# Header.net
KiCad netlist of a schematic drawn in Altium Designer
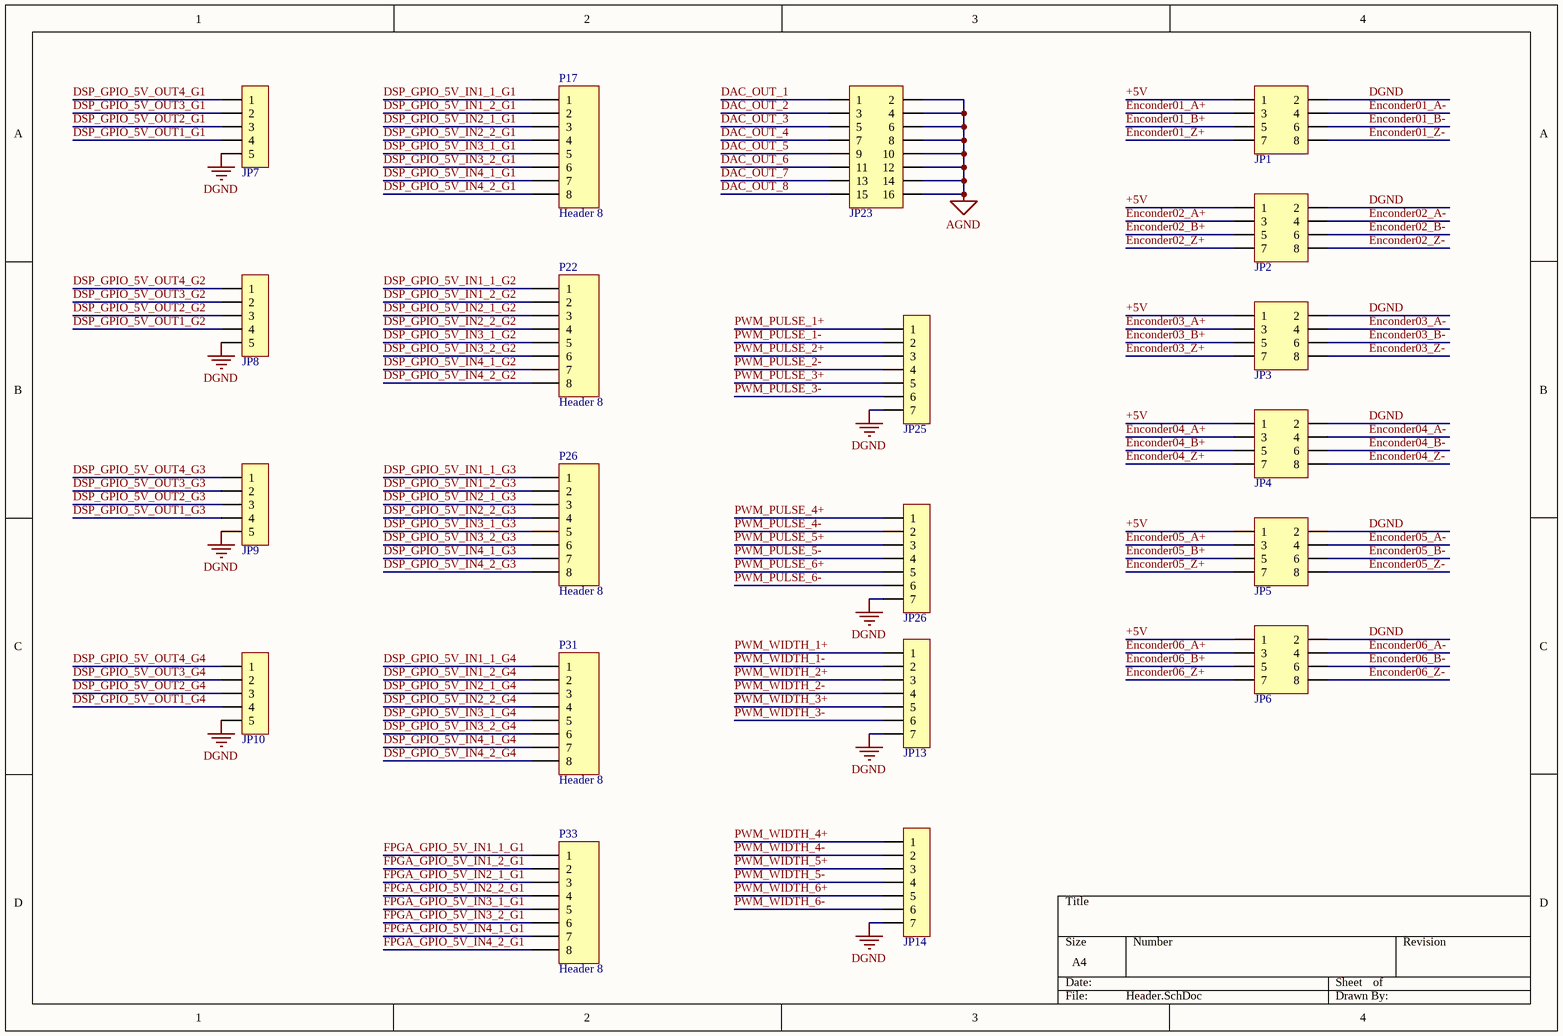
[diagram p0: Header.SchDoc]

(export (version "E")
  (design (tool "Eeschema 10.0.6"))
  (components
    (comp (ref "JP1")
      (value "Header 4X2")
      (footprint "connector5569R")
      (description "4*2P接插件")
      (fields (field (name "版权归属") "源创客"))
      (libsource (lib "4.4   - 接插件-脚距2.0") (part "Header 4X2"))
    )
    (comp (ref "JP2")
      (value "Header 4X2")
      (footprint "connector5569R")
      (description "4*2P接插件")
      (fields (field (name "版权归属") "源创客"))
      (libsource (lib "4.4   - 接插件-脚距2.0") (part "Header 4X2"))
    )
    (comp (ref "JP3")
      (value "Header 4X2")
      (footprint "connector5569R")
      (description "4*2P接插件")
      (fields (field (name "版权归属") "源创客"))
      (libsource (lib "4.4   - 接插件-脚距2.0") (part "Header 4X2"))
    )
    (comp (ref "JP4")
      (value "Header 4X2")
      (footprint "connector5569R")
      (description "4*2P接插件")
      (fields (field (name "版权归属") "源创客"))
      (libsource (lib "4.4   - 接插件-脚距2.0") (part "Header 4X2"))
    )
    (comp (ref "JP5")
      (value "Header 4X2")
      (footprint "connector5569R")
      (description "4*2P接插件")
      (fields (field (name "版权归属") "源创客"))
      (libsource (lib "4.4   - 接插件-脚距2.0") (part "Header 4X2"))
    )
    (comp (ref "JP6")
      (value "Header 4X2")
      (footprint "connector5569R")
      (description "4*2P接插件")
      (fields (field (name "版权归属") "源创客"))
      (libsource (lib "4.4   - 接插件-脚距2.0") (part "Header 4X2"))
    )
    (comp (ref "JP7")
      (value "HDR-1X5")
      (footprint "ZH1.5-WI-5P")
      (description "5P接插件")
      (fields (field (name "版权归属") "源创客"))
      (libsource (lib "4.3   - 接插件-脚距1.5") (part "Header 5"))
    )
    (comp (ref "JP8")
      (value "HDR-1X5")
      (footprint "ZH1.5-WI-5P")
      (description "5P接插件")
      (fields (field (name "版权归属") "源创客"))
      (libsource (lib "4.3   - 接插件-脚距1.5") (part "Header 5"))
    )
    (comp (ref "JP9")
      (value "HDR-1X5")
      (footprint "ZH1.5-WI-5P")
      (description "5P接插件")
      (fields (field (name "版权归属") "源创客"))
      (libsource (lib "4.3   - 接插件-脚距1.5") (part "Header 5"))
    )
    (comp (ref "JP10")
      (value "HDR-1X5")
      (footprint "ZH1.5-WI-5P")
      (description "5P接插件")
      (fields (field (name "版权归属") "源创客"))
      (libsource (lib "4.3   - 接插件-脚距1.5") (part "Header 5"))
    )
    (comp (ref "JP13")
      (value "HDR-1X7")
      (footprint "XH2.54-WI-7P")
      (description "7P接插件")
      (fields (field (name "版权归属") "源创客"))
      (libsource (lib "4.5   - 接插件-脚距2.54") (part "Header 7"))
    )
    (comp (ref "JP14")
      (value "HDR-1X7")
      (footprint "XH2.54-WI-7P")
      (description "7P接插件")
      (fields (field (name "版权归属") "源创客"))
      (libsource (lib "4.5   - 接插件-脚距2.54") (part "Header 7"))
    )
    (comp (ref "JP23")
      (value "Header 8X2")
      (footprint "connector558916pin")
      (description "8*2P接插件")
      (fields (field (name "版权归属") "源创客"))
      (libsource (lib "4.4   - 接插件-脚距2.0") (part "Header 8X2"))
    )
    (comp (ref "JP25")
      (value "HDR-1X7")
      (footprint "XH2.54-WI-7P")
      (description "7P接插件")
      (fields (field (name "版权归属") "源创客"))
      (libsource (lib "4.5   - 接插件-脚距2.54") (part "Header 7"))
    )
    (comp (ref "JP26")
      (value "HDR-1X7")
      (footprint "XH2.54-WI-7P")
      (description "7P接插件")
      (fields (field (name "版权归属") "源创客"))
      (libsource (lib "4.5   - 接插件-脚距2.54") (part "Header 7"))
    )
    (comp (ref "P17")
      (value "Header 8")
      (footprint "connector5569R")
      (description "Header, 8-Pin")
      (fields (field (name "PUBLISHER") "Altium Limited"))
      (libsource (lib "Miscellaneous Connectors") (part "Header 8"))
    )
    (comp (ref "P22")
      (value "Header 8")
      (footprint "connector5569R")
      (description "Header, 8-Pin")
      (fields (field (name "PUBLISHER") "Altium Limited"))
      (libsource (lib "Miscellaneous Connectors") (part "Header 8"))
    )
    (comp (ref "P26")
      (value "Header 8")
      (footprint "connector5569R")
      (description "Header, 8-Pin")
      (fields (field (name "PUBLISHER") "Altium Limited"))
      (libsource (lib "Miscellaneous Connectors") (part "Header 8"))
    )
    (comp (ref "P31")
      (value "Header 8")
      (footprint "connector5569R")
      (description "Header, 8-Pin")
      (fields (field (name "PUBLISHER") "Altium Limited"))
      (libsource (lib "Miscellaneous Connectors") (part "Header 8"))
    )
    (comp (ref "P33")
      (value "Header 8")
      (footprint "connector5569R")
      (description "Header, 8-Pin")
      (fields (field (name "PUBLISHER") "Altium Limited"))
      (libsource (lib "Miscellaneous Connectors") (part "Header 8"))
    )
  )
  (nets
    (net (code "1") (name "/+5V") (class "Default")
      (node (ref "JP1") (pin "1") (pinfunction "1_1") (pintype "passive"))
      (node (ref "JP2") (pin "1") (pinfunction "1_1") (pintype "passive"))
      (node (ref "JP3") (pin "1") (pinfunction "1_1") (pintype "passive"))
      (node (ref "JP4") (pin "1") (pinfunction "1_1") (pintype "passive"))
      (node (ref "JP5") (pin "1") (pinfunction "1_1") (pintype "passive"))
      (node (ref "JP6") (pin "1") (pinfunction "1_1") (pintype "passive"))
    )
    (net (code "2") (name "/DAC_OUT_1") (class "Default")
      (node (ref "JP23") (pin "1") (pinfunction "1_1") (pintype "passive"))
    )
    (net (code "3") (name "/DAC_OUT_2") (class "Default")
      (node (ref "JP23") (pin "3") (pinfunction "3_3") (pintype "passive"))
    )
    (net (code "4") (name "/DAC_OUT_3") (class "Default")
      (node (ref "JP23") (pin "5") (pinfunction "5_5") (pintype "passive"))
    )
    (net (code "5") (name "/DAC_OUT_4") (class "Default")
      (node (ref "JP23") (pin "7") (pinfunction "7_7") (pintype "passive"))
    )
    (net (code "6") (name "/DAC_OUT_5") (class "Default")
      (node (ref "JP23") (pin "9") (pinfunction "9_9") (pintype "passive"))
    )
    (net (code "7") (name "/DAC_OUT_6") (class "Default")
      (node (ref "JP23") (pin "11") (pinfunction "11_11") (pintype "passive"))
    )
    (net (code "8") (name "/DAC_OUT_7") (class "Default")
      (node (ref "JP23") (pin "13") (pinfunction "13_13") (pintype "passive"))
    )
    (net (code "9") (name "/DAC_OUT_8") (class "Default")
      (node (ref "JP23") (pin "15") (pinfunction "15_15") (pintype "passive"))
    )
    (net (code "10") (name "/DSP_GPIO_5V_IN1_1_G1") (class "Default")
      (node (ref "P17") (pin "1") (pinfunction "1_1") (pintype "passive"))
    )
    (net (code "11") (name "/DSP_GPIO_5V_IN1_1_G2") (class "Default")
      (node (ref "P22") (pin "1") (pinfunction "1_1") (pintype "passive"))
    )
    (net (code "12") (name "/DSP_GPIO_5V_IN1_1_G3") (class "Default")
      (node (ref "P26") (pin "1") (pinfunction "1_1") (pintype "passive"))
    )
    (net (code "13") (name "/DSP_GPIO_5V_IN1_1_G4") (class "Default")
      (node (ref "P31") (pin "1") (pinfunction "1_1") (pintype "passive"))
    )
    (net (code "14") (name "/DSP_GPIO_5V_IN1_2_G1") (class "Default")
      (node (ref "P17") (pin "2") (pinfunction "2_2") (pintype "passive"))
    )
    (net (code "15") (name "/DSP_GPIO_5V_IN1_2_G2") (class "Default")
      (node (ref "P22") (pin "2") (pinfunction "2_2") (pintype "passive"))
    )
    (net (code "16") (name "/DSP_GPIO_5V_IN1_2_G3") (class "Default")
      (node (ref "P26") (pin "2") (pinfunction "2_2") (pintype "passive"))
    )
    (net (code "17") (name "/DSP_GPIO_5V_IN1_2_G4") (class "Default")
      (node (ref "P31") (pin "2") (pinfunction "2_2") (pintype "passive"))
    )
    (net (code "18") (name "/DSP_GPIO_5V_IN2_1_G1") (class "Default")
      (node (ref "P17") (pin "3") (pinfunction "3_3") (pintype "passive"))
    )
    (net (code "19") (name "/DSP_GPIO_5V_IN2_1_G2") (class "Default")
      (node (ref "P22") (pin "3") (pinfunction "3_3") (pintype "passive"))
    )
    (net (code "20") (name "/DSP_GPIO_5V_IN2_1_G3") (class "Default")
      (node (ref "P26") (pin "3") (pinfunction "3_3") (pintype "passive"))
    )
    (net (code "21") (name "/DSP_GPIO_5V_IN2_1_G4") (class "Default")
      (node (ref "P31") (pin "3") (pinfunction "3_3") (pintype "passive"))
    )
    (net (code "22") (name "/DSP_GPIO_5V_IN2_2_G1") (class "Default")
      (node (ref "P17") (pin "4") (pinfunction "4_4") (pintype "passive"))
    )
    (net (code "23") (name "/DSP_GPIO_5V_IN2_2_G2") (class "Default")
      (node (ref "P22") (pin "4") (pinfunction "4_4") (pintype "passive"))
    )
    (net (code "24") (name "/DSP_GPIO_5V_IN2_2_G3") (class "Default")
      (node (ref "P26") (pin "4") (pinfunction "4_4") (pintype "passive"))
    )
    (net (code "25") (name "/DSP_GPIO_5V_IN2_2_G4") (class "Default")
      (node (ref "P31") (pin "4") (pinfunction "4_4") (pintype "passive"))
    )
    (net (code "26") (name "/DSP_GPIO_5V_IN3_1_G1") (class "Default")
      (node (ref "P17") (pin "5") (pinfunction "5_5") (pintype "passive"))
    )
    (net (code "27") (name "/DSP_GPIO_5V_IN3_1_G2") (class "Default")
      (node (ref "P22") (pin "5") (pinfunction "5_5") (pintype "passive"))
    )
    (net (code "28") (name "/DSP_GPIO_5V_IN3_1_G3") (class "Default")
      (node (ref "P26") (pin "5") (pinfunction "5_5") (pintype "passive"))
    )
    (net (code "29") (name "/DSP_GPIO_5V_IN3_1_G4") (class "Default")
      (node (ref "P31") (pin "5") (pinfunction "5_5") (pintype "passive"))
    )
    (net (code "30") (name "/DSP_GPIO_5V_IN3_2_G1") (class "Default")
      (node (ref "P17") (pin "6") (pinfunction "6_6") (pintype "passive"))
    )
    (net (code "31") (name "/DSP_GPIO_5V_IN3_2_G2") (class "Default")
      (node (ref "P22") (pin "6") (pinfunction "6_6") (pintype "passive"))
    )
    (net (code "32") (name "/DSP_GPIO_5V_IN3_2_G3") (class "Default")
      (node (ref "P26") (pin "6") (pinfunction "6_6") (pintype "passive"))
    )
    (net (code "33") (name "/DSP_GPIO_5V_IN3_2_G4") (class "Default")
      (node (ref "P31") (pin "6") (pinfunction "6_6") (pintype "passive"))
    )
    (net (code "34") (name "/DSP_GPIO_5V_IN4_1_G1") (class "Default")
      (node (ref "P17") (pin "7") (pinfunction "7_7") (pintype "passive"))
    )
    (net (code "35") (name "/DSP_GPIO_5V_IN4_1_G2") (class "Default")
      (node (ref "P22") (pin "7") (pinfunction "7_7") (pintype "passive"))
    )
    (net (code "36") (name "/DSP_GPIO_5V_IN4_1_G3") (class "Default")
      (node (ref "P26") (pin "7") (pinfunction "7_7") (pintype "passive"))
    )
    (net (code "37") (name "/DSP_GPIO_5V_IN4_1_G4") (class "Default")
      (node (ref "P31") (pin "7") (pinfunction "7_7") (pintype "passive"))
    )
    (net (code "38") (name "/DSP_GPIO_5V_IN4_2_G1") (class "Default")
      (node (ref "P17") (pin "8") (pinfunction "8_8") (pintype "passive"))
    )
    (net (code "39") (name "/DSP_GPIO_5V_IN4_2_G2") (class "Default")
      (node (ref "P22") (pin "8") (pinfunction "8_8") (pintype "passive"))
    )
    (net (code "40") (name "/DSP_GPIO_5V_IN4_2_G3") (class "Default")
      (node (ref "P26") (pin "8") (pinfunction "8_8") (pintype "passive"))
    )
    (net (code "41") (name "/DSP_GPIO_5V_IN4_2_G4") (class "Default")
      (node (ref "P31") (pin "8") (pinfunction "8_8") (pintype "passive"))
    )
    (net (code "42") (name "/DSP_GPIO_5V_OUT1_G1") (class "Default")
      (node (ref "JP7") (pin "4") (pinfunction "4_4") (pintype "passive"))
    )
    (net (code "43") (name "/DSP_GPIO_5V_OUT1_G2") (class "Default")
      (node (ref "JP8") (pin "4") (pinfunction "4_4") (pintype "passive"))
    )
    (net (code "44") (name "/DSP_GPIO_5V_OUT1_G3") (class "Default")
      (node (ref "JP9") (pin "4") (pinfunction "4_4") (pintype "passive"))
    )
    (net (code "45") (name "/DSP_GPIO_5V_OUT1_G4") (class "Default")
      (node (ref "JP10") (pin "4") (pinfunction "4_4") (pintype "passive"))
    )
    (net (code "46") (name "/DSP_GPIO_5V_OUT2_G1") (class "Default")
      (node (ref "JP7") (pin "3") (pinfunction "3_3") (pintype "passive"))
    )
    (net (code "47") (name "/DSP_GPIO_5V_OUT2_G2") (class "Default")
      (node (ref "JP8") (pin "3") (pinfunction "3_3") (pintype "passive"))
    )
    (net (code "48") (name "/DSP_GPIO_5V_OUT2_G3") (class "Default")
      (node (ref "JP9") (pin "3") (pinfunction "3_3") (pintype "passive"))
    )
    (net (code "49") (name "/DSP_GPIO_5V_OUT2_G4") (class "Default")
      (node (ref "JP10") (pin "3") (pinfunction "3_3") (pintype "passive"))
    )
    (net (code "50") (name "/DSP_GPIO_5V_OUT3_G1") (class "Default")
      (node (ref "JP7") (pin "2") (pinfunction "2_2") (pintype "passive"))
    )
    (net (code "51") (name "/DSP_GPIO_5V_OUT3_G2") (class "Default")
      (node (ref "JP8") (pin "2") (pinfunction "2_2") (pintype "passive"))
    )
    (net (code "52") (name "/DSP_GPIO_5V_OUT3_G3") (class "Default")
      (node (ref "JP9") (pin "2") (pinfunction "2_2") (pintype "passive"))
    )
    (net (code "53") (name "/DSP_GPIO_5V_OUT3_G4") (class "Default")
      (node (ref "JP10") (pin "2") (pinfunction "2_2") (pintype "passive"))
    )
    (net (code "54") (name "/DSP_GPIO_5V_OUT4_G1") (class "Default")
      (node (ref "JP7") (pin "1") (pinfunction "1_1") (pintype "passive"))
    )
    (net (code "55") (name "/DSP_GPIO_5V_OUT4_G2") (class "Default")
      (node (ref "JP8") (pin "1") (pinfunction "1_1") (pintype "passive"))
    )
    (net (code "56") (name "/DSP_GPIO_5V_OUT4_G3") (class "Default")
      (node (ref "JP9") (pin "1") (pinfunction "1_1") (pintype "passive"))
    )
    (net (code "57") (name "/DSP_GPIO_5V_OUT4_G4") (class "Default")
      (node (ref "JP10") (pin "1") (pinfunction "1_1") (pintype "passive"))
    )
    (net (code "58") (name "/Enconder01_A+") (class "Default")
      (node (ref "JP1") (pin "3") (pinfunction "3_3") (pintype "passive"))
    )
    (net (code "59") (name "/Enconder01_A-") (class "Default")
      (node (ref "JP1") (pin "4") (pinfunction "4_4") (pintype "passive"))
    )
    (net (code "60") (name "/Enconder01_B+") (class "Default")
      (node (ref "JP1") (pin "5") (pinfunction "5_5") (pintype "passive"))
    )
    (net (code "61") (name "/Enconder01_B-") (class "Default")
      (node (ref "JP1") (pin "6") (pinfunction "6_6") (pintype "passive"))
    )
    (net (code "62") (name "/Enconder01_Z+") (class "Default")
      (node (ref "JP1") (pin "7") (pinfunction "7_7") (pintype "passive"))
    )
    (net (code "63") (name "/Enconder01_Z-") (class "Default")
      (node (ref "JP1") (pin "8") (pinfunction "8_8") (pintype "passive"))
    )
    (net (code "64") (name "/Enconder02_A+") (class "Default")
      (node (ref "JP2") (pin "3") (pinfunction "3_3") (pintype "passive"))
    )
    (net (code "65") (name "/Enconder02_A-") (class "Default")
      (node (ref "JP2") (pin "4") (pinfunction "4_4") (pintype "passive"))
    )
    (net (code "66") (name "/Enconder02_B+") (class "Default")
      (node (ref "JP2") (pin "5") (pinfunction "5_5") (pintype "passive"))
    )
    (net (code "67") (name "/Enconder02_B-") (class "Default")
      (node (ref "JP2") (pin "6") (pinfunction "6_6") (pintype "passive"))
    )
    (net (code "68") (name "/Enconder02_Z+") (class "Default")
      (node (ref "JP2") (pin "7") (pinfunction "7_7") (pintype "passive"))
    )
    (net (code "69") (name "/Enconder02_Z-") (class "Default")
      (node (ref "JP2") (pin "8") (pinfunction "8_8") (pintype "passive"))
    )
    (net (code "70") (name "/Enconder03_A+") (class "Default")
      (node (ref "JP3") (pin "3") (pinfunction "3_3") (pintype "passive"))
    )
    (net (code "71") (name "/Enconder03_A-") (class "Default")
      (node (ref "JP3") (pin "4") (pinfunction "4_4") (pintype "passive"))
    )
    (net (code "72") (name "/Enconder03_B+") (class "Default")
      (node (ref "JP3") (pin "5") (pinfunction "5_5") (pintype "passive"))
    )
    (net (code "73") (name "/Enconder03_B-") (class "Default")
      (node (ref "JP3") (pin "6") (pinfunction "6_6") (pintype "passive"))
    )
    (net (code "74") (name "/Enconder03_Z+") (class "Default")
      (node (ref "JP3") (pin "7") (pinfunction "7_7") (pintype "passive"))
    )
    (net (code "75") (name "/Enconder03_Z-") (class "Default")
      (node (ref "JP3") (pin "8") (pinfunction "8_8") (pintype "passive"))
    )
    (net (code "76") (name "/Enconder04_A+") (class "Default")
      (node (ref "JP4") (pin "3") (pinfunction "3_3") (pintype "passive"))
    )
    (net (code "77") (name "/Enconder04_A-") (class "Default")
      (node (ref "JP4") (pin "4") (pinfunction "4_4") (pintype "passive"))
    )
    (net (code "78") (name "/Enconder04_B+") (class "Default")
      (node (ref "JP4") (pin "5") (pinfunction "5_5") (pintype "passive"))
    )
    (net (code "79") (name "/Enconder04_B-") (class "Default")
      (node (ref "JP4") (pin "6") (pinfunction "6_6") (pintype "passive"))
    )
    (net (code "80") (name "/Enconder04_Z+") (class "Default")
      (node (ref "JP4") (pin "7") (pinfunction "7_7") (pintype "passive"))
    )
    (net (code "81") (name "/Enconder04_Z-") (class "Default")
      (node (ref "JP4") (pin "8") (pinfunction "8_8") (pintype "passive"))
    )
    (net (code "82") (name "/Enconder05_A+") (class "Default")
      (node (ref "JP5") (pin "3") (pinfunction "3_3") (pintype "passive"))
    )
    (net (code "83") (name "/Enconder05_A-") (class "Default")
      (node (ref "JP5") (pin "4") (pinfunction "4_4") (pintype "passive"))
    )
    (net (code "84") (name "/Enconder05_B+") (class "Default")
      (node (ref "JP5") (pin "5") (pinfunction "5_5") (pintype "passive"))
    )
    (net (code "85") (name "/Enconder05_B-") (class "Default")
      (node (ref "JP5") (pin "6") (pinfunction "6_6") (pintype "passive"))
    )
    (net (code "86") (name "/Enconder05_Z+") (class "Default")
      (node (ref "JP5") (pin "7") (pinfunction "7_7") (pintype "passive"))
    )
    (net (code "87") (name "/Enconder05_Z-") (class "Default")
      (node (ref "JP5") (pin "8") (pinfunction "8_8") (pintype "passive"))
    )
    (net (code "88") (name "/Enconder06_A+") (class "Default")
      (node (ref "JP6") (pin "3") (pinfunction "3_3") (pintype "passive"))
    )
    (net (code "89") (name "/Enconder06_A-") (class "Default")
      (node (ref "JP6") (pin "4") (pinfunction "4_4") (pintype "passive"))
    )
    (net (code "90") (name "/Enconder06_B+") (class "Default")
      (node (ref "JP6") (pin "5") (pinfunction "5_5") (pintype "passive"))
    )
    (net (code "91") (name "/Enconder06_B-") (class "Default")
      (node (ref "JP6") (pin "6") (pinfunction "6_6") (pintype "passive"))
    )
    (net (code "92") (name "/Enconder06_Z+") (class "Default")
      (node (ref "JP6") (pin "7") (pinfunction "7_7") (pintype "passive"))
    )
    (net (code "93") (name "/Enconder06_Z-") (class "Default")
      (node (ref "JP6") (pin "8") (pinfunction "8_8") (pintype "passive"))
    )
    (net (code "94") (name "/FPGA_GPIO_5V_IN1_1_G1") (class "Default")
      (node (ref "P33") (pin "1") (pinfunction "1_1") (pintype "passive"))
    )
    (net (code "95") (name "/FPGA_GPIO_5V_IN1_2_G1") (class "Default")
      (node (ref "P33") (pin "2") (pinfunction "2_2") (pintype "passive"))
    )
    (net (code "96") (name "/FPGA_GPIO_5V_IN2_1_G1") (class "Default")
      (node (ref "P33") (pin "3") (pinfunction "3_3") (pintype "passive"))
    )
    (net (code "97") (name "/FPGA_GPIO_5V_IN2_2_G1") (class "Default")
      (node (ref "P33") (pin "4") (pinfunction "4_4") (pintype "passive"))
    )
    (net (code "98") (name "/FPGA_GPIO_5V_IN3_1_G1") (class "Default")
      (node (ref "P33") (pin "5") (pinfunction "5_5") (pintype "passive"))
    )
    (net (code "99") (name "/FPGA_GPIO_5V_IN3_2_G1") (class "Default")
      (node (ref "P33") (pin "6") (pinfunction "6_6") (pintype "passive"))
    )
    (net (code "100") (name "/FPGA_GPIO_5V_IN4_1_G1") (class "Default")
      (node (ref "P33") (pin "7") (pinfunction "7_7") (pintype "passive"))
    )
    (net (code "101") (name "/FPGA_GPIO_5V_IN4_2_G1") (class "Default")
      (node (ref "P33") (pin "8") (pinfunction "8_8") (pintype "passive"))
    )
    (net (code "102") (name "/PWM_PULSE_1+") (class "Default")
      (node (ref "JP25") (pin "1") (pinfunction "1_1") (pintype "passive"))
    )
    (net (code "103") (name "/PWM_PULSE_1-") (class "Default")
      (node (ref "JP25") (pin "2") (pinfunction "2_2") (pintype "passive"))
    )
    (net (code "104") (name "/PWM_PULSE_2+") (class "Default")
      (node (ref "JP25") (pin "3") (pinfunction "3_3") (pintype "passive"))
    )
    (net (code "105") (name "/PWM_PULSE_2-") (class "Default")
      (node (ref "JP25") (pin "4") (pinfunction "4_4") (pintype "passive"))
    )
    (net (code "106") (name "/PWM_PULSE_3+") (class "Default")
      (node (ref "JP25") (pin "5") (pinfunction "5_5") (pintype "passive"))
    )
    (net (code "107") (name "/PWM_PULSE_3-") (class "Default")
      (node (ref "JP25") (pin "6") (pinfunction "6_6") (pintype "passive"))
    )
    (net (code "108") (name "/PWM_PULSE_4+") (class "Default")
      (node (ref "JP26") (pin "1") (pinfunction "1_1") (pintype "passive"))
    )
    (net (code "109") (name "/PWM_PULSE_4-") (class "Default")
      (node (ref "JP26") (pin "2") (pinfunction "2_2") (pintype "passive"))
    )
    (net (code "110") (name "/PWM_PULSE_5+") (class "Default")
      (node (ref "JP26") (pin "3") (pinfunction "3_3") (pintype "passive"))
    )
    (net (code "111") (name "/PWM_PULSE_5-") (class "Default")
      (node (ref "JP26") (pin "4") (pinfunction "4_4") (pintype "passive"))
    )
    (net (code "112") (name "/PWM_PULSE_6+") (class "Default")
      (node (ref "JP26") (pin "5") (pinfunction "5_5") (pintype "passive"))
    )
    (net (code "113") (name "/PWM_PULSE_6-") (class "Default")
      (node (ref "JP26") (pin "6") (pinfunction "6_6") (pintype "passive"))
    )
    (net (code "114") (name "/PWM_WIDTH_1+") (class "Default")
      (node (ref "JP13") (pin "1") (pinfunction "1_1") (pintype "passive"))
    )
    (net (code "115") (name "/PWM_WIDTH_1-") (class "Default")
      (node (ref "JP13") (pin "2") (pinfunction "2_2") (pintype "passive"))
    )
    (net (code "116") (name "/PWM_WIDTH_2+") (class "Default")
      (node (ref "JP13") (pin "3") (pinfunction "3_3") (pintype "passive"))
    )
    (net (code "117") (name "/PWM_WIDTH_2-") (class "Default")
      (node (ref "JP13") (pin "4") (pinfunction "4_4") (pintype "passive"))
    )
    (net (code "118") (name "/PWM_WIDTH_3+") (class "Default")
      (node (ref "JP13") (pin "5") (pinfunction "5_5") (pintype "passive"))
    )
    (net (code "119") (name "/PWM_WIDTH_3-") (class "Default")
      (node (ref "JP13") (pin "6") (pinfunction "6_6") (pintype "passive"))
    )
    (net (code "120") (name "/PWM_WIDTH_4+") (class "Default")
      (node (ref "JP14") (pin "1") (pinfunction "1_1") (pintype "passive"))
    )
    (net (code "121") (name "/PWM_WIDTH_4-") (class "Default")
      (node (ref "JP14") (pin "2") (pinfunction "2_2") (pintype "passive"))
    )
    (net (code "122") (name "/PWM_WIDTH_5+") (class "Default")
      (node (ref "JP14") (pin "3") (pinfunction "3_3") (pintype "passive"))
    )
    (net (code "123") (name "/PWM_WIDTH_5-") (class "Default")
      (node (ref "JP14") (pin "4") (pinfunction "4_4") (pintype "passive"))
    )
    (net (code "124") (name "/PWM_WIDTH_6+") (class "Default")
      (node (ref "JP14") (pin "5") (pinfunction "5_5") (pintype "passive"))
    )
    (net (code "125") (name "/PWM_WIDTH_6-") (class "Default")
      (node (ref "JP14") (pin "6") (pinfunction "6_6") (pintype "passive"))
    )
    (net (code "126") (name "AGND") (class "Default")
      (node (ref "JP23") (pin "10") (pinfunction "10_10") (pintype "passive"))
      (node (ref "JP23") (pin "12") (pinfunction "12_12") (pintype "passive"))
      (node (ref "JP23") (pin "14") (pinfunction "14_14") (pintype "passive"))
      (node (ref "JP23") (pin "16") (pinfunction "16_16") (pintype "passive"))
      (node (ref "JP23") (pin "2") (pinfunction "2_2") (pintype "passive"))
      (node (ref "JP23") (pin "4") (pinfunction "4_4") (pintype "passive"))
      (node (ref "JP23") (pin "6") (pinfunction "6_6") (pintype "passive"))
      (node (ref "JP23") (pin "8") (pinfunction "8_8") (pintype "passive"))
    )
    (net (code "127") (name "DGND") (class "Default")
      (node (ref "JP1") (pin "2") (pinfunction "2_2") (pintype "passive"))
      (node (ref "JP10") (pin "5") (pinfunction "5_5") (pintype "passive"))
      (node (ref "JP13") (pin "7") (pinfunction "7_7") (pintype "passive"))
      (node (ref "JP14") (pin "7") (pinfunction "7_7") (pintype "passive"))
      (node (ref "JP2") (pin "2") (pinfunction "2_2") (pintype "passive"))
      (node (ref "JP25") (pin "7") (pinfunction "7_7") (pintype "passive"))
      (node (ref "JP26") (pin "7") (pinfunction "7_7") (pintype "passive"))
      (node (ref "JP3") (pin "2") (pinfunction "2_2") (pintype "passive"))
      (node (ref "JP4") (pin "2") (pinfunction "2_2") (pintype "passive"))
      (node (ref "JP5") (pin "2") (pinfunction "2_2") (pintype "passive"))
      (node (ref "JP6") (pin "2") (pinfunction "2_2") (pintype "passive"))
      (node (ref "JP7") (pin "5") (pinfunction "5_5") (pintype "passive"))
      (node (ref "JP8") (pin "5") (pinfunction "5_5") (pintype "passive"))
      (node (ref "JP9") (pin "5") (pinfunction "5_5") (pintype "passive"))
    )
  )
)
